# Pilot.net
KiCad netlist of a schematic drawn in Altium Designer
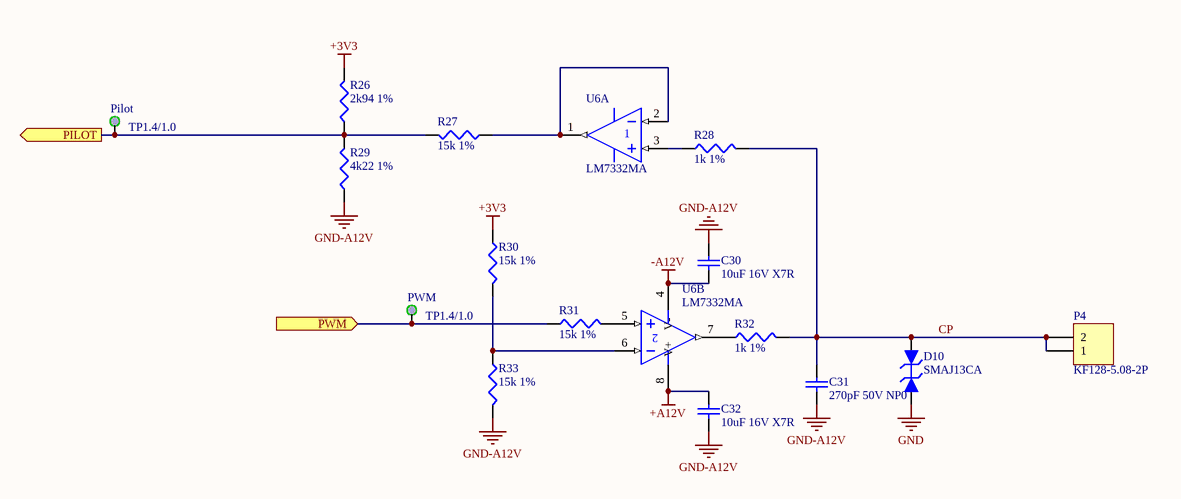
[diagram p0: Pilot.SchDoc]

(export (version "E")
  (design (tool "Eeschema 10.0.6"))
  (components
    (comp (ref "C30")
      (value "10uF 16V X7R")
      (footprint "IPC-7352 Chip_Capacitor_N:CAPC3216N")
      (description "Ceramic Capactor")
      (fields (field (name "PUBLISHER") "Altium Limited"))
      (libsource (lib "Miscellaneous Devices") (part "Cap Semi"))
    )
    (comp (ref "C31")
      (value "270pF 50V NP0")
      (footprint "IPC-7352 Chip_Capacitor_N:CAPC2012N")
      (description "Capactor")
      (fields (field (name "PUBLISHER") "Altium Limited"))
      (libsource (lib "Miscellaneous Devices") (part "Cap Semi"))
    )
    (comp (ref "C32")
      (value "10uF 16V X7R")
      (footprint "IPC-7352 Chip_Capacitor_N:CAPC3216N")
      (description "Ceramic Capactor")
      (fields (field (name "PUBLISHER") "Altium Limited"))
      (libsource (lib "Miscellaneous Devices") (part "Cap Semi"))
    )
    (comp (ref "D10")
      (value "SMAJ13CA")
      (footprint "Small Outline Diode - 2 C-Bend Leads:DSO-C2/G1.6")
      (description "Bidirectional zener diode")
      (fields (field (name "MANUFACTURER") "ON"))
      (libsource (lib "UserSchlib") (part "Zener bidirectional"))
    )
    (comp (ref "P4")
      (value "KF128-5.08-2P")
      (footprint "UserPcbLib:KF128-5.08-2P")
      (description "Connector 2-Pin")
      (fields (field (name "PUBLISHER") "Altium Limited"))
      (libsource (lib "Miscellaneous Connectors") (part "Header 2"))
    )
    (comp (ref "Pilot")
      (value "TP1.4/1.0")
      (footprint "UserPcbLib:TP1.4/1.0")
      (libsource (lib "UserSchlib") (part "TP1.4/1.0"))
    )
    (comp (ref "PWM")
      (value "TP1.4/1.0")
      (footprint "UserPcbLib:TP1.4/1.0")
      (libsource (lib "UserSchlib") (part "TP1.4/1.0"))
    )
    (comp (ref "R26")
      (value "2k94 1%")
      (footprint "IPC-7352 Chip_Resistor_N:RESC2012N")
      (description "Resistor")
      (libsource (lib "Miscellaneous Devices") (part "Res3"))
    )
    (comp (ref "R27")
      (value "15k 1%")
      (footprint "IPC-7352 Chip_Resistor_N:RESC2012N")
      (description "Resistor")
      (libsource (lib "Miscellaneous Devices") (part "Res3"))
    )
    (comp (ref "R28")
      (value "1k 1%")
      (footprint "IPC-7352 Chip_Resistor_N:RESC2012N")
      (description "Resistor")
      (libsource (lib "Miscellaneous Devices") (part "Res3"))
    )
    (comp (ref "R29")
      (value "4k22 1%")
      (footprint "IPC-7352 Chip_Resistor_N:RESC2012N")
      (description "Resistor")
      (libsource (lib "Miscellaneous Devices") (part "Res3"))
    )
    (comp (ref "R30")
      (value "15k 1%")
      (footprint "IPC-7352 Chip_Resistor_N:RESC2012N")
      (description "Resistor")
      (libsource (lib "Miscellaneous Devices") (part "Res3"))
    )
    (comp (ref "R31")
      (value "15k 1%")
      (footprint "IPC-7352 Chip_Resistor_N:RESC2012N")
      (description "Resistor")
      (libsource (lib "Miscellaneous Devices") (part "Res3"))
    )
    (comp (ref "R32")
      (value "1k 1%")
      (footprint "IPC-7352 Chip_Resistor_N:RESC2012N")
      (description "Resistor")
      (libsource (lib "Miscellaneous Devices") (part "Res3"))
    )
    (comp (ref "R33")
      (value "15k 1%")
      (footprint "IPC-7352 Chip_Resistor_N:RESC2012N")
      (description "Resistor")
      (libsource (lib "Miscellaneous Devices") (part "Res3"))
    )
    (comp (ref "U6")
      (value "LM7332MA")
      (footprint "D008_M")
      (description "Dual Operational Amplifier")
      (fields (field (name "MANUFACTURER") "TI") (field (name "PUBLISHER") "Altium Limited"))
      (libsource (lib "TI Operational Amplifier") (part "LM258D"))
    )
  )
  (nets
    (net (code "1") (name "+3V3") (class "Default")
      (node (ref "R26") (pin "2") (pinfunction "2_2") (pintype "passive"))
      (node (ref "R30") (pin "1") (pinfunction "1_1") (pintype "passive"))
    )
    (net (code "2") (name "+A12V") (class "Default")
      (node (ref "C32") (pin "2") (pinfunction "2_2") (pintype "passive"))
      (node (ref "U6") (pin "8") (pinfunction "V+_8") (pintype "power_in"))
    )
    (net (code "3") (name "-A12V") (class "Default")
      (node (ref "C30") (pin "1") (pinfunction "1_1") (pintype "passive"))
      (node (ref "U6") (pin "4") (pinfunction "V-_4") (pintype "power_in"))
    )
    (net (code "4") (name "/CP") (class "Default")
      (node (ref "C31") (pin "2") (pinfunction "2_2") (pintype "passive"))
      (node (ref "D10") (pin "2") (pinfunction "2_2") (pintype "passive"))
      (node (ref "P4") (pin "1") (pinfunction "1_1") (pintype "passive"))
      (node (ref "P4") (pin "2") (pinfunction "2_2") (pintype "passive"))
      (node (ref "R28") (pin "2") (pinfunction "2_2") (pintype "passive"))
      (node (ref "R32") (pin "2") (pinfunction "2_2") (pintype "passive"))
    )
    (net (code "5") (name "/PILOT") (class "Default")
      (node (ref "Pilot") (pin "1") (pinfunction "1_1") (pintype "passive"))
      (node (ref "R26") (pin "1") (pinfunction "1_1") (pintype "passive"))
      (node (ref "R27") (pin "2") (pinfunction "2_2") (pintype "passive"))
      (node (ref "R29") (pin "2") (pinfunction "2_2") (pintype "passive"))
    )
    (net (code "6") (name "/PWM") (class "Default")
      (node (ref "PWM") (pin "1") (pinfunction "1_1") (pintype "passive"))
      (node (ref "R31") (pin "1") (pinfunction "1_1") (pintype "passive"))
    )
    (net (code "7") (name "GND") (class "Default")
      (node (ref "D10") (pin "1") (pinfunction "1_1") (pintype "passive"))
    )
    (net (code "8") (name "GND-A12V") (class "Default")
      (node (ref "C30") (pin "2") (pinfunction "2_2") (pintype "passive"))
      (node (ref "C31") (pin "1") (pinfunction "1_1") (pintype "passive"))
      (node (ref "C32") (pin "1") (pinfunction "1_1") (pintype "passive"))
      (node (ref "R29") (pin "1") (pinfunction "1_1") (pintype "passive"))
      (node (ref "R33") (pin "2") (pinfunction "2_2") (pintype "passive"))
    )
    (net (code "9") (name "Net-(U6A-IN+)") (class "Default")
      (node (ref "R28") (pin "1") (pinfunction "1_1") (pintype "passive"))
      (node (ref "U6") (pin "3") (pinfunction "IN+_3") (pintype "input"))
    )
    (net (code "10") (name "Net-(U6A-IN-)") (class "Default")
      (node (ref "R27") (pin "1") (pinfunction "1_1") (pintype "passive"))
      (node (ref "U6") (pin "1") (pinfunction "OUT_1") (pintype "output"))
      (node (ref "U6") (pin "2") (pinfunction "IN-_2") (pintype "input"))
    )
    (net (code "11") (name "Net-(U6B-IN+)") (class "Default")
      (node (ref "R31") (pin "2") (pinfunction "2_2") (pintype "passive"))
      (node (ref "U6") (pin "5") (pinfunction "IN+_5") (pintype "input"))
    )
    (net (code "12") (name "Net-(U6B-IN-)") (class "Default")
      (node (ref "R30") (pin "2") (pinfunction "2_2") (pintype "passive"))
      (node (ref "R33") (pin "1") (pinfunction "1_1") (pintype "passive"))
      (node (ref "U6") (pin "6") (pinfunction "IN-_6") (pintype "input"))
    )
    (net (code "13") (name "Net-(U6B-OUT)") (class "Default")
      (node (ref "R32") (pin "1") (pinfunction "1_1") (pintype "passive"))
      (node (ref "U6") (pin "7") (pinfunction "OUT_7") (pintype "output"))
    )
    (net (code "14") (name "V+") (class "Default")
      (node (ref "U6") (pin "8") (pinfunction "V+_8") (pintype "power_in"))
    )
    (net (code "15") (name "V-") (class "Default")
      (node (ref "U6") (pin "4") (pinfunction "V-_4") (pintype "power_in"))
    )
  )
)
